# napajeni.net
KiCad netlist of a schematic drawn in Altium Designer
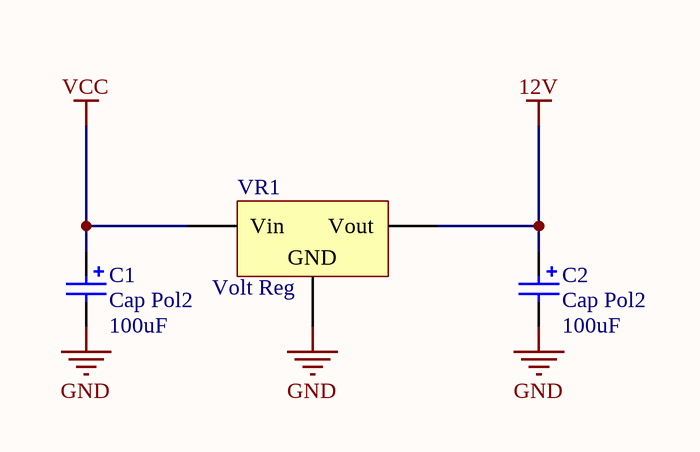
[diagram p0: napajeni.SchDoc]

(export (version "E")
  (design (tool "Eeschema 10.0.6"))
  (components
    (comp (ref "C1")
      (value "Cap Pol2")
      (footprint "POLAR0.8")
      (description "Polarized Capacitor (Axial)")
      (fields (field (name "ALTIUM_VALUE") "100uF") (field (name "PUBLISHER") "Altium Limited"))
      (libsource (lib "Miscellaneous Devices") (part "Cap Pol2"))
    )
    (comp (ref "C2")
      (value "Cap Pol2")
      (footprint "POLAR0.8")
      (description "Polarized Capacitor (Axial)")
      (fields (field (name "ALTIUM_VALUE") "100uF") (field (name "PUBLISHER") "Altium Limited"))
      (libsource (lib "Miscellaneous Devices") (part "Cap Pol2"))
    )
    (comp (ref "VR1")
      (value "Volt Reg")
      (footprint "D2PAK_N")
      (description "Voltage Regulator")
      (fields (field (name "PUBLISHER") "Altium Limited"))
      (libsource (lib "Miscellaneous Devices") (part "Volt Reg"))
    )
  )
  (nets
    (net (code "1") (name "12V") (class "Default")
      (node (ref "C2") (pin "1") (pinfunction "1_1") (pintype "passive"))
      (node (ref "VR1") (pin "3") (pinfunction "Vout_3") (pintype "passive"))
    )
    (net (code "2") (name "GND") (class "Default")
      (node (ref "C1") (pin "2") (pinfunction "2_2") (pintype "passive"))
      (node (ref "C2") (pin "2") (pinfunction "2_2") (pintype "passive"))
      (node (ref "VR1") (pin "2") (pinfunction "GND_2") (pintype "passive"))
    )
    (net (code "3") (name "VCC") (class "Default")
      (node (ref "C1") (pin "1") (pinfunction "1_1") (pintype "passive"))
      (node (ref "VR1") (pin "1") (pinfunction "Vin_1") (pintype "passive"))
    )
  )
)
